# V1_0.net
KiCad netlist of a schematic drawn in Altium Designer
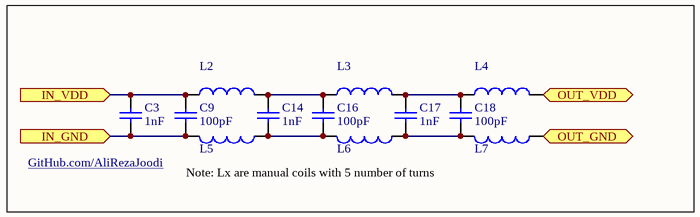
[diagram p0: V1.0.SchDoc]

(export (version "E")
  (design (tool "Eeschema 10.0.6"))
  (components
    (comp (ref "C3")
      (value "1nF")
      (footprint "CAPNTO2.54-3.56x2.03")
      (description "Capacitor")
      (fields (field (name "MANUFACTURER") "Generic Components") (field (name "PUBLISHER") "Altium Limited"))
      (libsource (lib "Miscellaneous Devices") (part "Cap"))
    )
    (comp (ref "C9")
      (value "100pF")
      (footprint "CAPNTO2.54-3.56x2.03")
      (description "Capacitor")
      (fields (field (name "MANUFACTURER") "Generic Components") (field (name "PUBLISHER") "Altium Limited"))
      (libsource (lib "Miscellaneous Devices") (part "Cap"))
    )
    (comp (ref "C14")
      (value "1nF")
      (footprint "CAPNTO2.54-3.56x2.03")
      (description "Capacitor")
      (fields (field (name "MANUFACTURER") "Generic Components") (field (name "PUBLISHER") "Altium Limited"))
      (libsource (lib "Miscellaneous Devices") (part "Cap"))
    )
    (comp (ref "C16")
      (value "100pF")
      (footprint "CAPNTO2.54-3.56x2.03")
      (description "Capacitor")
      (fields (field (name "MANUFACTURER") "Generic Components") (field (name "PUBLISHER") "Altium Limited"))
      (libsource (lib "Miscellaneous Devices") (part "Cap"))
    )
    (comp (ref "C17")
      (value "1nF")
      (footprint "CAPNTO2.54-3.56x2.03")
      (description "Capacitor")
      (fields (field (name "MANUFACTURER") "Generic Components") (field (name "PUBLISHER") "Altium Limited"))
      (libsource (lib "Miscellaneous Devices") (part "Cap"))
    )
    (comp (ref "C18")
      (value "100pF")
      (footprint "CAPNTO2.54-3.56x2.03")
      (description "Capacitor")
      (fields (field (name "MANUFACTURER") "Generic Components") (field (name "PUBLISHER") "Altium Limited"))
      (libsource (lib "Miscellaneous Devices") (part "Cap"))
    )
    (comp (ref "L2")
      (value "5N")
      (footprint "CAPPR5-6.3x11")
      (description "Inductor")
      (fields (field (name "MANUFACTURER") "Generic Components") (field (name "PUBLISHER") "Altium Limited"))
      (libsource (lib "my Libraries") (part "Inductor"))
    )
    (comp (ref "L3")
      (value "5N")
      (footprint "CAPPR5-6.3x11")
      (description "Inductor")
      (fields (field (name "MANUFACTURER") "Generic Components") (field (name "PUBLISHER") "Altium Limited"))
      (libsource (lib "my Libraries") (part "Inductor"))
    )
    (comp (ref "L4")
      (value "5N")
      (footprint "CAPPR5-6.3x11")
      (description "Inductor")
      (fields (field (name "MANUFACTURER") "Generic Components") (field (name "PUBLISHER") "Altium Limited"))
      (libsource (lib "my Libraries") (part "Inductor"))
    )
    (comp (ref "L5")
      (value "5N")
      (footprint "CAPPR5-6.3x11")
      (description "Inductor")
      (fields (field (name "MANUFACTURER") "Generic Components") (field (name "PUBLISHER") "Altium Limited"))
      (libsource (lib "") (part "Inductor_1"))
    )
    (comp (ref "L6")
      (value "5N")
      (footprint "CAPPR5-6.3x11")
      (description "Inductor")
      (fields (field (name "MANUFACTURER") "Generic Components") (field (name "PUBLISHER") "Altium Limited"))
      (libsource (lib "") (part "Inductor_1"))
    )
    (comp (ref "L7")
      (value "5N")
      (footprint "CAPPR5-6.3x11")
      (description "Inductor")
      (fields (field (name "MANUFACTURER") "Generic Components") (field (name "PUBLISHER") "Altium Limited"))
      (libsource (lib "") (part "Inductor_1"))
    )
  )
  (nets
    (net (code "1") (name "/IN_GND") (class "Default")
      (node (ref "C3") (pin "1") (pinfunction "1_1") (pintype "passive"))
      (node (ref "C9") (pin "1") (pinfunction "1_1") (pintype "passive"))
      (node (ref "L5") (pin "2") (pinfunction "2_2") (pintype "passive"))
    )
    (net (code "2") (name "/IN_VDD") (class "Default")
      (node (ref "C3") (pin "2") (pinfunction "2_2") (pintype "passive"))
      (node (ref "C9") (pin "2") (pinfunction "2_2") (pintype "passive"))
      (node (ref "L2") (pin "2") (pinfunction "2_2") (pintype "passive"))
    )
    (net (code "3") (name "/OUT_GND") (class "Default")
      (node (ref "L7") (pin "1") (pinfunction "1_1") (pintype "passive"))
    )
    (net (code "4") (name "/OUT_VDD") (class "Default")
      (node (ref "L4") (pin "1") (pinfunction "1_1") (pintype "passive"))
    )
    (net (code "5") (name "Net-(C14-Pad1)") (class "Default")
      (node (ref "C14") (pin "1") (pinfunction "1_1") (pintype "passive"))
      (node (ref "C16") (pin "1") (pinfunction "1_1") (pintype "passive"))
      (node (ref "L5") (pin "1") (pinfunction "1_1") (pintype "passive"))
      (node (ref "L6") (pin "2") (pinfunction "2_2") (pintype "passive"))
    )
    (net (code "6") (name "Net-(C14-Pad2)") (class "Default")
      (node (ref "C14") (pin "2") (pinfunction "2_2") (pintype "passive"))
      (node (ref "C16") (pin "2") (pinfunction "2_2") (pintype "passive"))
      (node (ref "L2") (pin "1") (pinfunction "1_1") (pintype "passive"))
      (node (ref "L3") (pin "2") (pinfunction "2_2") (pintype "passive"))
    )
    (net (code "7") (name "Net-(C17-Pad1)") (class "Default")
      (node (ref "C17") (pin "1") (pinfunction "1_1") (pintype "passive"))
      (node (ref "C18") (pin "1") (pinfunction "1_1") (pintype "passive"))
      (node (ref "L6") (pin "1") (pinfunction "1_1") (pintype "passive"))
      (node (ref "L7") (pin "2") (pinfunction "2_2") (pintype "passive"))
    )
    (net (code "8") (name "Net-(C17-Pad2)") (class "Default")
      (node (ref "C17") (pin "2") (pinfunction "2_2") (pintype "passive"))
      (node (ref "C18") (pin "2") (pinfunction "2_2") (pintype "passive"))
      (node (ref "L3") (pin "1") (pinfunction "1_1") (pintype "passive"))
      (node (ref "L4") (pin "2") (pinfunction "2_2") (pintype "passive"))
    )
  )
)
